# 12_RK3568_OSCPLLPMUIO.net
KiCad netlist of a schematic drawn in Altium Designer
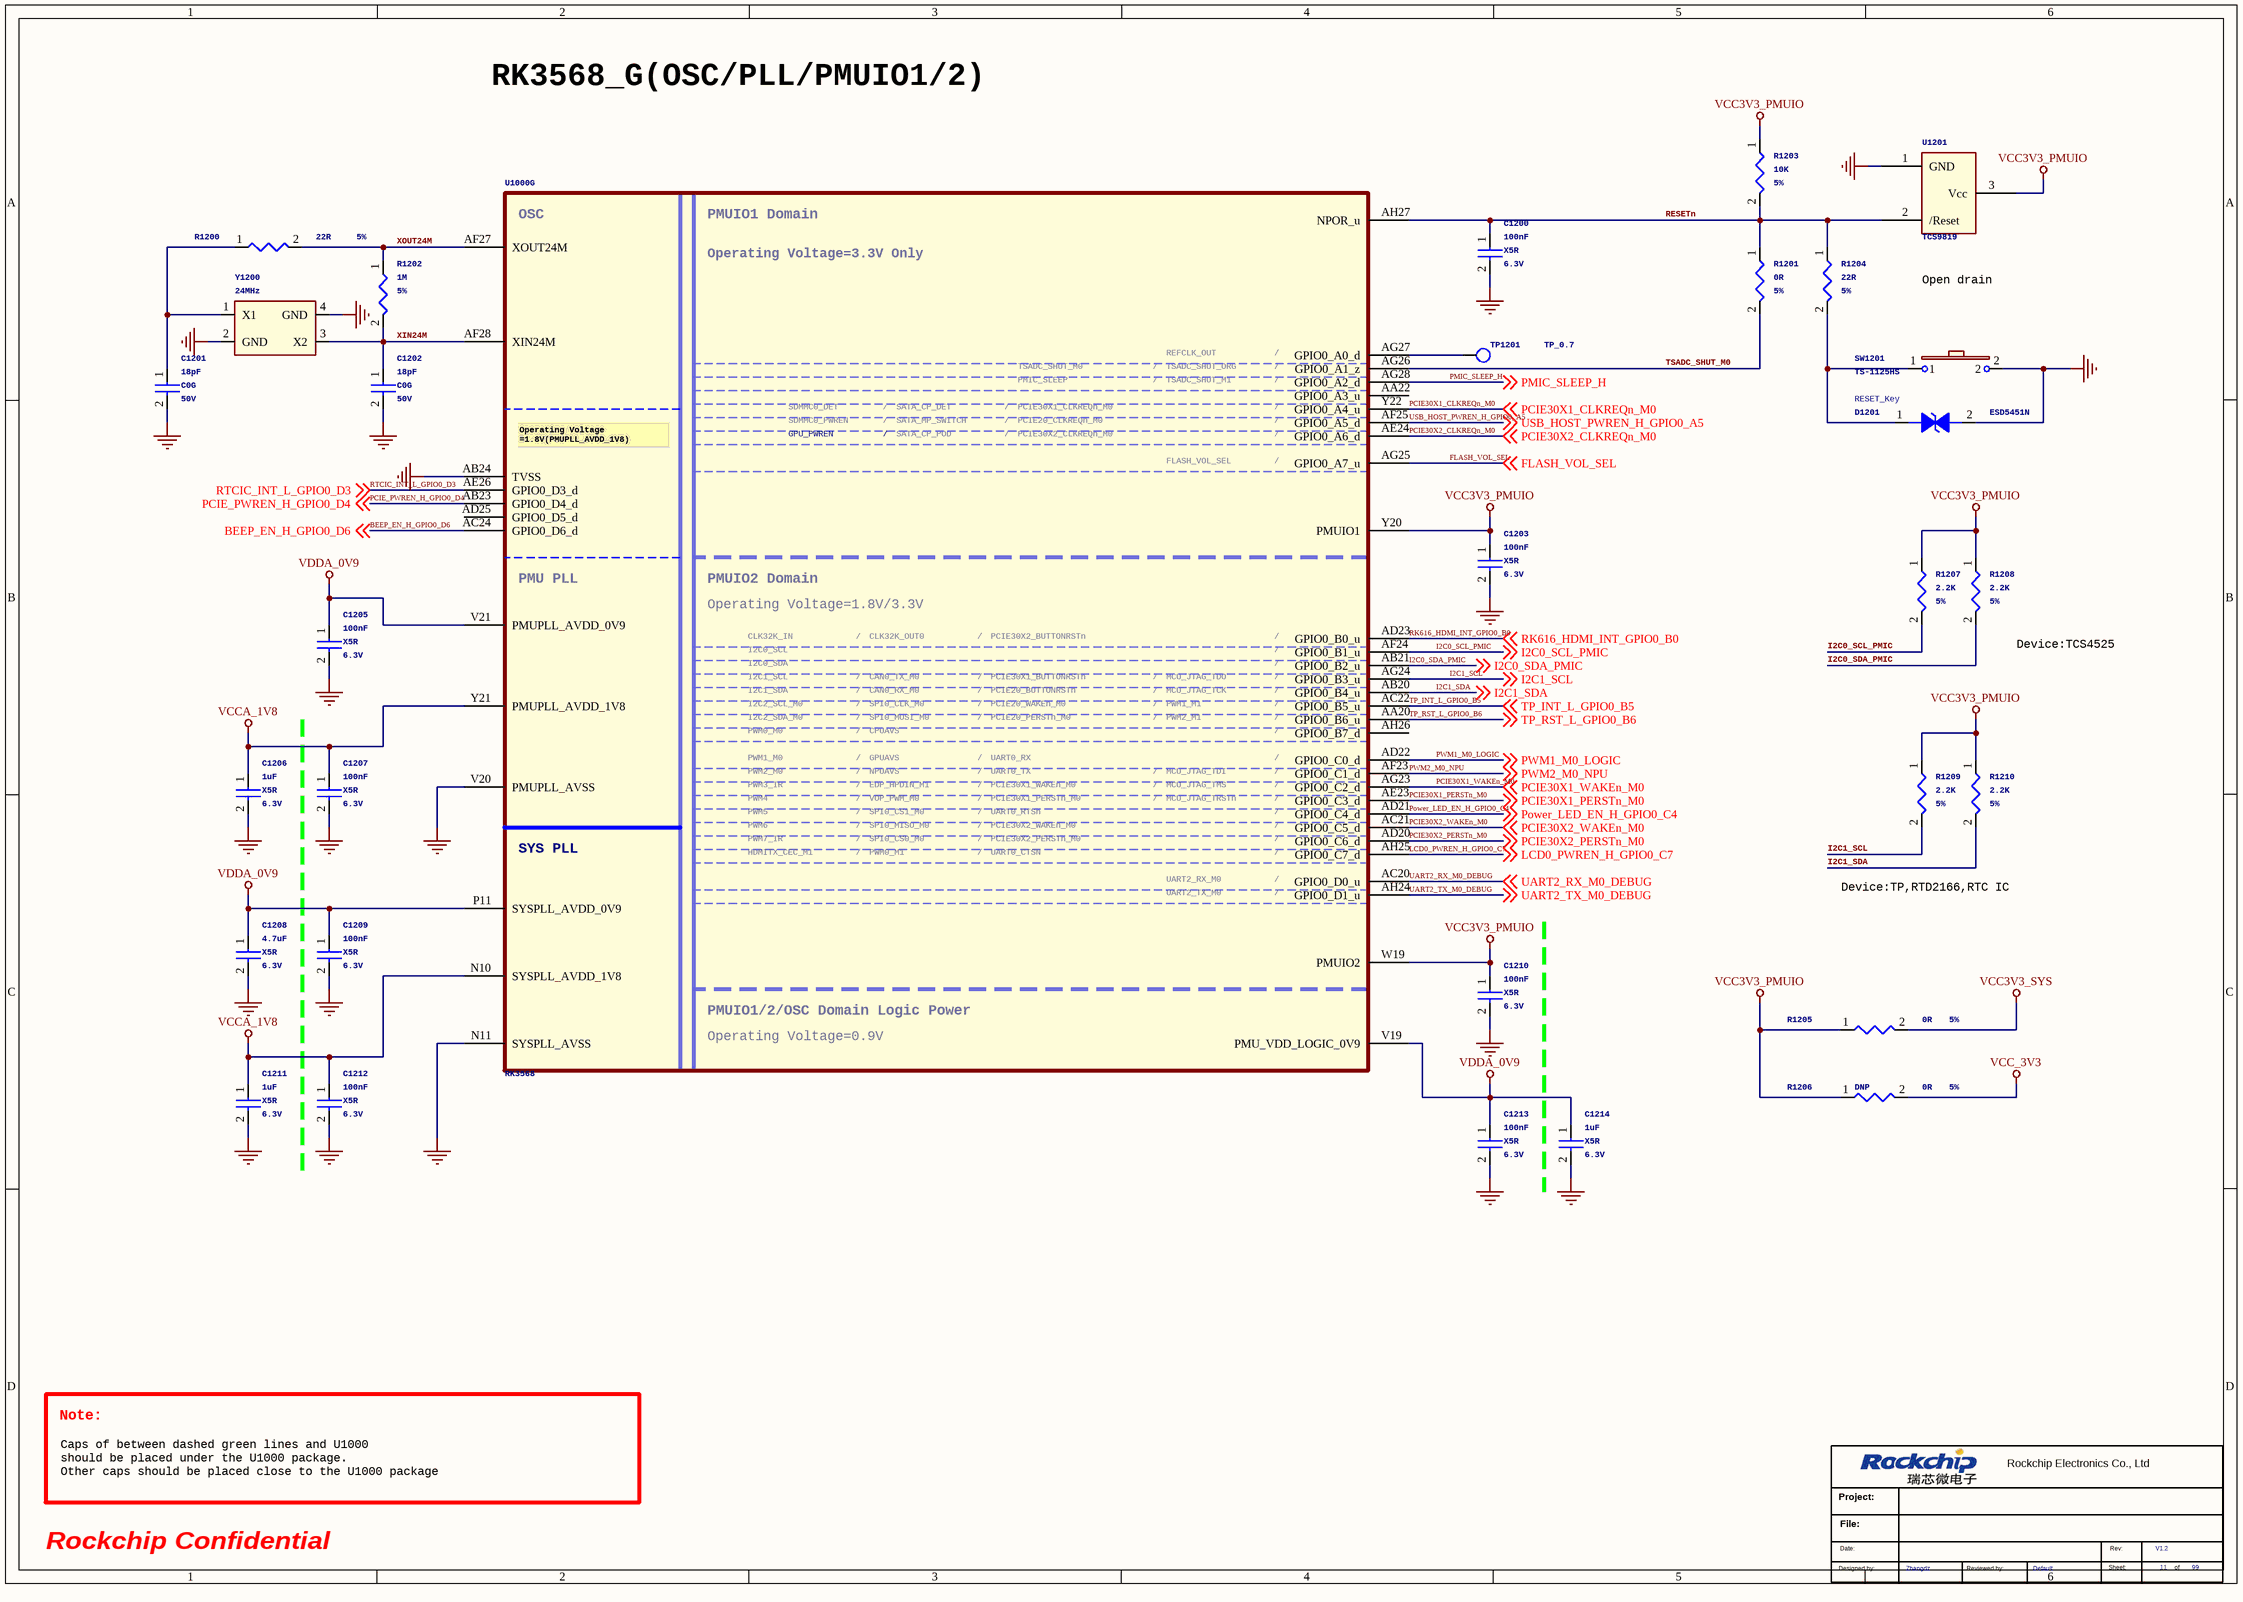
[diagram p0: 12.RK3568_OSCPLLPMUIO.SchDoc]

(export (version "E")
  (design (tool "Eeschema 10.0.6"))
  (components
    (comp (ref "*")
      (value "Rockchip_new")
      (fields
        (field (name "SCHEMATIC PAGE COUNT") "99")
        (field (name "SCHEMATIC PAGE NUMBER") "11")
        (field (name "DESIGNER") "Zhangdz")
        (field (name "REVISION") "V1.2")
        (field (name "CHECK") "Default")
      )
      (libsource (lib "*") (part "Rockchip_new"))
    )
    (comp (ref "C1200")
      (value "100nF")
      (footprint "C0201")
      (description "cap,100.00nF,+/-10%,6.3V,X5R,C0201")
      (fields
        (field (name "VOLTAGE") "6.3V")
        (field (name "DIELECTRIC") "X5R")
        (field (name "TOLERANCE") "10%")
        (field (name "MANUFACTURER") "TDK")
        (field (name "CREATED BY") "JJJ")
      )
      (libsource (lib "*") (part "CAP NP"))
    )
    (comp (ref "C1201")
      (value "18pF")
      (footprint "C0402")
      (description "cap,18.00pF,+/-5%,50V,C0G,C0402")
      (fields
        (field (name "VOLTAGE") "50V")
        (field (name "DIELECTRIC") "C0G")
        (field (name "TOLERANCE") "5%")
        (field (name "MANUFACTURER") "TDK")
        (field (name "CREATED BY") "JJJ")
      )
      (libsource (lib "*") (part "CAP NP"))
    )
    (comp (ref "C1202")
      (value "18pF")
      (footprint "C0402")
      (description "cap,18.00pF,+/-5%,50V,C0G,C0402")
      (fields
        (field (name "VOLTAGE") "50V")
        (field (name "DIELECTRIC") "C0G")
        (field (name "MANUFACTURER") "TDK")
        (field (name "TOLERANCE") "5%")
        (field (name "CREATED BY") "JJJ")
      )
      (libsource (lib "*") (part "CAP NP"))
    )
    (comp (ref "C1203")
      (value "100nF")
      (footprint "C0201")
      (description "cap,100.00nF,+/-10%,6.3V,X5R,C0201")
      (fields
        (field (name "VOLTAGE") "6.3V")
        (field (name "DIELECTRIC") "X5R")
        (field (name "MANUFACTURER") "TDK")
        (field (name "TOLERANCE") "10%")
        (field (name "CREATED BY") "JJJ")
      )
      (libsource (lib "*") (part "CAP NP"))
    )
    (comp (ref "C1205")
      (value "100nF")
      (footprint "C0201")
      (description "cap,100.00nF,+/-10%,6.3V,X5R,C0201")
      (fields
        (field (name "VOLTAGE") "6.3V")
        (field (name "DIELECTRIC") "X5R")
        (field (name "MANUFACTURER") "TDK")
        (field (name "TOLERANCE") "10%")
        (field (name "CREATED BY") "JJJ")
      )
      (libsource (lib "*") (part "CAP NP"))
    )
    (comp (ref "C1206")
      (value "1uF")
      (footprint "C0402")
      (description "cap,1.00uF,+/-10%,6.3V,X5R,C0402")
      (fields
        (field (name "VOLTAGE") "6.3V")
        (field (name "DIELECTRIC") "X5R")
        (field (name "MANUFACTURER") "TDK")
        (field (name "TOLERANCE") "10%")
        (field (name "CREATED BY") "JJJ")
      )
      (libsource (lib "*") (part "CAP NP"))
    )
    (comp (ref "C1207")
      (value "100nF")
      (footprint "C0201")
      (description "cap,100.00nF,+/-10%,6.3V,X5R,C0201")
      (fields
        (field (name "VOLTAGE") "6.3V")
        (field (name "DIELECTRIC") "X5R")
        (field (name "TOLERANCE") "10%")
        (field (name "MANUFACTURER") "TDK")
        (field (name "CREATED BY") "JJJ")
      )
      (libsource (lib "*") (part "CAP NP"))
    )
    (comp (ref "C1208")
      (value "4.7uF")
      (footprint "C0402")
      (description "cap,4.70uF,+/-10%,6.3V,X5R,C0402")
      (fields
        (field (name "VOLTAGE") "6.3V")
        (field (name "DIELECTRIC") "X5R")
        (field (name "TOLERANCE") "10%")
        (field (name "MANUFACTURER") "TDK")
        (field (name "CREATED BY") "JJJ")
      )
      (libsource (lib "*") (part "CAP NP"))
    )
    (comp (ref "C1209")
      (value "100nF")
      (footprint "C0201")
      (description "cap,100.00nF,+/-10%,6.3V,X5R,C0201")
      (fields
        (field (name "VOLTAGE") "6.3V")
        (field (name "DIELECTRIC") "X5R")
        (field (name "MANUFACTURER") "TDK")
        (field (name "TOLERANCE") "10%")
        (field (name "CREATED BY") "JJJ")
      )
      (libsource (lib "*") (part "CAP NP"))
    )
    (comp (ref "C1210")
      (value "100nF")
      (footprint "C0201")
      (description "cap,100.00nF,+/-10%,6.3V,X5R,C0201")
      (fields
        (field (name "VOLTAGE") "6.3V")
        (field (name "DIELECTRIC") "X5R")
        (field (name "MANUFACTURER") "TDK")
        (field (name "TOLERANCE") "10%")
        (field (name "CREATED BY") "JJJ")
      )
      (libsource (lib "*") (part "CAP NP"))
    )
    (comp (ref "C1211")
      (value "1uF")
      (footprint "C0402")
      (description "cap,1.00uF,+/-10%,6.3V,X5R,C0402")
      (fields
        (field (name "VOLTAGE") "6.3V")
        (field (name "DIELECTRIC") "X5R")
        (field (name "MANUFACTURER") "TDK")
        (field (name "TOLERANCE") "10%")
        (field (name "CREATED BY") "JJJ")
      )
      (libsource (lib "*") (part "CAP NP"))
    )
    (comp (ref "C1212")
      (value "100nF")
      (footprint "C0201")
      (description "cap,100.00nF,+/-10%,6.3V,X5R,C0201")
      (fields
        (field (name "VOLTAGE") "6.3V")
        (field (name "DIELECTRIC") "X5R")
        (field (name "TOLERANCE") "10%")
        (field (name "MANUFACTURER") "TDK")
        (field (name "CREATED BY") "JJJ")
      )
      (libsource (lib "*") (part "CAP NP"))
    )
    (comp (ref "C1213")
      (value "100nF")
      (footprint "C0201")
      (description "cap,100.00nF,+/-10%,6.3V,X5R,C0201")
      (fields
        (field (name "VOLTAGE") "6.3V")
        (field (name "DIELECTRIC") "X5R")
        (field (name "TOLERANCE") "10%")
        (field (name "MANUFACTURER") "TDK")
        (field (name "CREATED BY") "JJJ")
      )
      (libsource (lib "*") (part "CAP NP"))
    )
    (comp (ref "C1214")
      (value "1uF")
      (footprint "C0402")
      (description "cap,1.00uF,+/-10%,6.3V,X5R,C0402")
      (fields
        (field (name "VOLTAGE") "6.3V")
        (field (name "DIELECTRIC") "X5R")
        (field (name "TOLERANCE") "10%")
        (field (name "MANUFACTURER") "TDK")
        (field (name "CREATED BY") "JJJ")
      )
      (libsource (lib "*") (part "CAP NP"))
    )
    (comp (ref "D1201")
      (value "ESD5451N")
      (footprint "ESD0402")
      (description "1-Line, Bi-directional, Transient Voltage Suppressors.17.5pF.")
      (fields (field (name "MANUFACTURER") "WillSemi(韦尔半导体)") (field (name "CREATED BY") "JJJ"))
      (libsource (lib "*") (part "DIODE BI_DIR TRIG"))
    )
    (comp (ref "R1200")
      (value "22R")
      (footprint "R0402")
      (description "通用厚膜电阻,22R,+/-5%,R0402,1/16W.")
      (fields
        (field (name "TOLERANCE") "5%")
        (field (name "MANUFACTURER") "YAGEO")
        (field (name "CREATED BY") "YTL")
      )
      (libsource (lib "*") (part "RESISTOR"))
    )
    (comp (ref "R1201")
      (value "0R")
      (footprint "R0402")
      (description "通用厚膜电阻,0R,+/-5%,R0402,1/16W.")
      (fields
        (field (name "TOLERANCE") "5%")
        (field (name "MANUFACTURER") "YAGEO")
        (field (name "CREATED BY") "YTL")
      )
      (libsource (lib "*") (part "RESISTOR"))
    )
    (comp (ref "R1202")
      (value "1M")
      (footprint "R0402")
      (description "通用厚膜电阻,1M,+/-5%,R0402,1/16W.")
      (fields
        (field (name "TOLERANCE") "5%")
        (field (name "MANUFACTURER") "YAGEO")
        (field (name "CREATED BY") "YTL")
      )
      (libsource (lib "*") (part "RESISTOR"))
    )
    (comp (ref "R1203")
      (value "10K")
      (footprint "R0402")
      (description "通用厚膜电阻,10K,+/-5%,R0402,1/16W.")
      (fields
        (field (name "TOLERANCE") "5%")
        (field (name "MANUFACTURER") "YAGEO")
        (field (name "CREATED BY") "YTL")
      )
      (libsource (lib "*") (part "RESISTOR"))
    )
    (comp (ref "R1204")
      (value "22R")
      (footprint "R0402")
      (description "通用厚膜电阻,22R,+/-5%,R0402,1/16W.")
      (fields
        (field (name "TOLERANCE") "5%")
        (field (name "MANUFACTURER") "YAGEO")
        (field (name "CREATED BY") "YTL")
      )
      (libsource (lib "*") (part "RESISTOR"))
    )
    (comp (ref "R1205")
      (value "0R")
      (footprint "R0402")
      (description "通用厚膜电阻,0R,+/-5%,R0402,1/16W.")
      (fields
        (field (name "TOLERANCE") "5%")
        (field (name "MANUFACTURER") "YAGEO")
        (field (name "CREATED BY") "YTL")
      )
      (libsource (lib "*") (part "RESISTOR"))
    )
    (comp (ref "R1206")
      (value "0R")
      (footprint "R0402")
      (description "通用厚膜电阻,0R,+/-5%,R0402,1/16W.")
      (fields
        (field (name "TOLERANCE") "5%")
        (field (name "OPTION") "DNP")
        (field (name "MANUFACTURER") "YAGEO")
        (field (name "CREATED BY") "YTL")
      )
      (libsource (lib "*") (part "RESISTOR"))
    )
    (comp (ref "R1207")
      (value "2.2K")
      (footprint "R0402")
      (description "通用厚膜电阻,2K2,+/-5%,R0402,1/16W.")
      (fields
        (field (name "TOLERANCE") "5%")
        (field (name "MANUFACTURER") "YAGEO")
        (field (name "CREATED BY") "YTL")
      )
      (libsource (lib "*") (part "RESISTOR"))
    )
    (comp (ref "R1208")
      (value "2.2K")
      (footprint "R0402")
      (description "通用厚膜电阻,2K2,+/-5%,R0402,1/16W.")
      (fields
        (field (name "TOLERANCE") "5%")
        (field (name "MANUFACTURER") "YAGEO")
        (field (name "CREATED BY") "YTL")
      )
      (libsource (lib "*") (part "RESISTOR"))
    )
    (comp (ref "R1209")
      (value "2.2K")
      (footprint "R0402")
      (description "通用厚膜电阻,2K2,+/-5%,R0402,1/16W.")
      (fields
        (field (name "TOLERANCE") "5%")
        (field (name "MANUFACTURER") "YAGEO")
        (field (name "CREATED BY") "YTL")
      )
      (libsource (lib "*") (part "RESISTOR"))
    )
    (comp (ref "R1210")
      (value "2.2K")
      (footprint "R0402")
      (description "通用厚膜电阻,2K2,+/-5%,R0402,1/16W.")
      (fields
        (field (name "TOLERANCE") "5%")
        (field (name "MANUFACTURER") "YAGEO")
        (field (name "CREATED BY") "YTL")
      )
      (libsource (lib "*") (part "RESISTOR"))
    )
    (comp (ref "SW1201")
      (value "TS-1125HS")
      (footprint "SW2_6R00X3R70X2R50")
      (description "2脚贴片，6MMx3.7MM按键")
      (fields
        (field (name "OPTION") "RESET_Key")
        (field (name "MANUFACTURER") "褀华电子")
        (field (name "CREATED BY") "YWQ")
      )
      (libsource (lib "*") (part "KEY_2PIN"))
    )
    (comp (ref "TP1201")
      (value "TP_0.7")
      (footprint "TP_0R70")
      (description "Test Point 0.7mm")
      (fields (field (name "CREATED BY") "JJJ"))
      (libsource (lib "*") (part "TP"))
    )
    (comp (ref "U1000")
      (value "RK3568")
      (footprint "BGA636_19R00X19R00X1R20")
      (description "ROCKCHIP SOC")
      (fields (field (name "MANUFACTURER") "Rockchip (瑞芯微)") (field (name "CREATED BY") "JJJ"))
      (libsource (lib "*") (part "SOC_RK3568"))
    )
    (comp (ref "U1201")
      (value "TCS9819")
      (footprint "SOT_23")
      (description "Ultra-Small Built-In Delay High-Precision Voltage Detector")
      (fields (field (name "MANUFACTURER") "Chipower（芯力微）") (field (name "CREATED BY") "JJJ"))
      (libsource (lib "*") (part "Voltage_Detector_CE8809"))
    )
    (comp (ref "Y1200")
      (value "24MHz")
      (footprint "CRY4_3R20X2R50X0R80")
      (description "无源晶振，24M，3225,±10ppm，8pF，Hosonic")
      (fields (field (name "MANUFACTURER") "Hosonic(鸿星电子)") (field (name "CREATED BY") "JJJ"))
      (libsource (lib "*") (part "CRYSTAL_4P"))
    )
  )
  (nets
    (net (code "1") (name "/RESETn") (class "Default")
      (node (ref "C1200") (pin "1") (pinfunction "1_1") (pintype "passive"))
      (node (ref "R1201") (pin "1") (pinfunction "1_1") (pintype "passive"))
      (node (ref "R1203") (pin "2") (pinfunction "2_2") (pintype "passive"))
      (node (ref "R1204") (pin "1") (pinfunction "1_1") (pintype "passive"))
      (node (ref "U1000") (pin "AH27") (pinfunction "NPOR_u_AH27") (pintype "passive"))
      (node (ref "U1201") (pin "2") (pinfunction "/Reset_2") (pintype "passive"))
    )
    (net (code "2") (name "/TSADC_SHUT_M0") (class "Default")
      (node (ref "R1201") (pin "2") (pinfunction "2_2") (pintype "passive"))
      (node (ref "U1000") (pin "AG26") (pinfunction "GPIO0_A1_z_AG26") (pintype "passive"))
    )
    (net (code "3") (name "/XIN24M") (class "Default")
      (node (ref "C1202") (pin "1") (pinfunction "1_1") (pintype "passive"))
      (node (ref "R1202") (pin "2") (pinfunction "2_2") (pintype "passive"))
      (node (ref "U1000") (pin "AF28") (pinfunction "XIN24M_AF28") (pintype "passive"))
      (node (ref "Y1200") (pin "3") (pinfunction "X2_3") (pintype "passive"))
    )
    (net (code "4") (name "/XOUT24M") (class "Default")
      (node (ref "R1200") (pin "2") (pinfunction "2_2") (pintype "passive"))
      (node (ref "R1202") (pin "1") (pinfunction "1_1") (pintype "passive"))
      (node (ref "U1000") (pin "AF27") (pinfunction "XOUT24M_AF27") (pintype "passive"))
    )
    (net (code "5") (name "BEEP_EN_H_GPIO0_D6") (class "Default")
      (node (ref "U1000") (pin "AC24") (pinfunction "GPIO0_D6_d_AC24") (pintype "passive"))
    )
    (net (code "6") (name "FLASH_VOL_SEL") (class "Default")
      (node (ref "U1000") (pin "AG25") (pinfunction "GPIO0_A7_u_AG25") (pintype "passive"))
    )
    (net (code "7") (name "GND") (class "Default")
      (node (ref "C1200") (pin "2") (pinfunction "2_2") (pintype "passive"))
      (node (ref "C1201") (pin "2") (pinfunction "2_2") (pintype "passive"))
      (node (ref "C1202") (pin "2") (pinfunction "2_2") (pintype "passive"))
      (node (ref "C1203") (pin "2") (pinfunction "2_2") (pintype "passive"))
      (node (ref "C1205") (pin "2") (pinfunction "2_2") (pintype "passive"))
      (node (ref "C1206") (pin "2") (pinfunction "2_2") (pintype "passive"))
      (node (ref "C1207") (pin "2") (pinfunction "2_2") (pintype "passive"))
      (node (ref "C1208") (pin "2") (pinfunction "2_2") (pintype "passive"))
      (node (ref "C1209") (pin "2") (pinfunction "2_2") (pintype "passive"))
      (node (ref "C1210") (pin "2") (pinfunction "2_2") (pintype "passive"))
      (node (ref "C1211") (pin "2") (pinfunction "2_2") (pintype "passive"))
      (node (ref "C1212") (pin "2") (pinfunction "2_2") (pintype "passive"))
      (node (ref "C1213") (pin "2") (pinfunction "2_2") (pintype "passive"))
      (node (ref "C1214") (pin "2") (pinfunction "2_2") (pintype "passive"))
      (node (ref "D1201") (pin "2") (pinfunction "2_2") (pintype "passive"))
      (node (ref "SW1201") (pin "2") (pinfunction "2_2") (pintype "passive"))
      (node (ref "U1000") (pin "AB24") (pinfunction "TVSS_AB24") (pintype "passive"))
      (node (ref "U1000") (pin "N11") (pinfunction "SYSPLL_AVSS_N11") (pintype "passive"))
      (node (ref "U1000") (pin "V20") (pinfunction "PMUPLL_AVSS_V20") (pintype "passive"))
      (node (ref "U1201") (pin "1") (pinfunction "GND_1") (pintype "passive"))
      (node (ref "Y1200") (pin "2") (pinfunction "GND_2") (pintype "power_in"))
      (node (ref "Y1200") (pin "4") (pinfunction "GND_4") (pintype "power_in"))
    )
    (net (code "8") (name "I2C0_SCL_PMIC") (class "Default")
      (node (ref "R1207") (pin "2") (pinfunction "2_2") (pintype "passive"))
      (node (ref "U1000") (pin "AF24") (pinfunction "GPIO0_B1_u_AF24") (pintype "passive"))
    )
    (net (code "9") (name "I2C0_SDA_PMIC") (class "Default")
      (node (ref "R1208") (pin "2") (pinfunction "2_2") (pintype "passive"))
      (node (ref "U1000") (pin "AB21") (pinfunction "GPIO0_B2_u_AB21") (pintype "passive"))
    )
    (net (code "10") (name "I2C1_SCL") (class "Default")
      (node (ref "R1209") (pin "2") (pinfunction "2_2") (pintype "passive"))
      (node (ref "U1000") (pin "AG24") (pinfunction "GPIO0_B3_u_AG24") (pintype "passive"))
    )
    (net (code "11") (name "I2C1_SDA") (class "Default")
      (node (ref "R1210") (pin "2") (pinfunction "2_2") (pintype "passive"))
      (node (ref "U1000") (pin "AB20") (pinfunction "GPIO0_B4_u_AB20") (pintype "passive"))
    )
    (net (code "12") (name "LCD0_PWREN_H_GPIO0_C7") (class "Default")
      (node (ref "U1000") (pin "AH25") (pinfunction "GPIO0_C7_d_AH25") (pintype "passive"))
    )
    (net (code "13") (name "Net-(D1201-Pad1)") (class "Default")
      (node (ref "D1201") (pin "1") (pinfunction "1_1") (pintype "passive"))
      (node (ref "R1204") (pin "2") (pinfunction "2_2") (pintype "passive"))
      (node (ref "SW1201") (pin "1") (pinfunction "1_1") (pintype "passive"))
    )
    (net (code "14") (name "Net-(U1000G-GPIO0_A0_d)") (class "Default")
      (node (ref "TP1201") (pin "1") (pinfunction "1_1") (pintype "passive"))
      (node (ref "U1000") (pin "AG27") (pinfunction "GPIO0_A0_d_AG27") (pintype "passive"))
    )
    (net (code "15") (name "Net-(Y1200-X1)") (class "Default")
      (node (ref "C1201") (pin "1") (pinfunction "1_1") (pintype "passive"))
      (node (ref "R1200") (pin "1") (pinfunction "1_1") (pintype "passive"))
      (node (ref "Y1200") (pin "1") (pinfunction "X1_1") (pintype "passive"))
    )
    (net (code "16") (name "PCIE30X1_CLKREQn_M0") (class "Default")
      (node (ref "U1000") (pin "Y22") (pinfunction "GPIO0_A4_u_Y22") (pintype "passive"))
    )
    (net (code "17") (name "PCIE30X1_PERSTn_M0") (class "Default")
      (node (ref "U1000") (pin "AE23") (pinfunction "GPIO0_C3_d_AE23") (pintype "passive"))
    )
    (net (code "18") (name "PCIE30X1_WAKEn_M0") (class "Default")
      (node (ref "U1000") (pin "AG23") (pinfunction "GPIO0_C2_d_AG23") (pintype "passive"))
    )
    (net (code "19") (name "PCIE30X2_CLKREQn_M0") (class "Default")
      (node (ref "U1000") (pin "AE24") (pinfunction "GPIO0_A6_d_AE24") (pintype "passive"))
    )
    (net (code "20") (name "PCIE30X2_PERSTn_M0") (class "Default")
      (node (ref "U1000") (pin "AD20") (pinfunction "GPIO0_C6_d_AD20") (pintype "passive"))
    )
    (net (code "21") (name "PCIE30X2_WAKEn_M0") (class "Default")
      (node (ref "U1000") (pin "AC21") (pinfunction "GPIO0_C5_d_AC21") (pintype "passive"))
    )
    (net (code "22") (name "PCIE_PWREN_H_GPIO0_D4") (class "Default")
      (node (ref "U1000") (pin "AB23") (pinfunction "GPIO0_D4_d_AB23") (pintype "passive"))
    )
    (net (code "23") (name "PMIC_SLEEP_H") (class "Default")
      (node (ref "U1000") (pin "AG28") (pinfunction "GPIO0_A2_d_AG28") (pintype "passive"))
    )
    (net (code "24") (name "PWM1_M0_LOGIC") (class "Default")
      (node (ref "U1000") (pin "AD22") (pinfunction "GPIO0_C0_d_AD22") (pintype "passive"))
    )
    (net (code "25") (name "PWM2_M0_NPU") (class "Default")
      (node (ref "U1000") (pin "AF23") (pinfunction "GPIO0_C1_d_AF23") (pintype "passive"))
    )
    (net (code "26") (name "Power_LED_EN_H_GPIO0_C4") (class "Default")
      (node (ref "U1000") (pin "AD21") (pinfunction "GPIO0_C4_d_AD21") (pintype "passive"))
    )
    (net (code "27") (name "RK616_HDMI_INT_GPIO0_B0") (class "Default")
      (node (ref "U1000") (pin "AD23") (pinfunction "GPIO0_B0_u_AD23") (pintype "passive"))
    )
    (net (code "28") (name "RTCIC_INT_L_GPIO0_D3") (class "Default")
      (node (ref "U1000") (pin "AE26") (pinfunction "GPIO0_D3_d_AE26") (pintype "passive"))
    )
    (net (code "29") (name "TP_INT_L_GPIO0_B5") (class "Default")
      (node (ref "U1000") (pin "AC22") (pinfunction "GPIO0_B5_u_AC22") (pintype "passive"))
    )
    (net (code "30") (name "TP_RST_L_GPIO0_B6") (class "Default")
      (node (ref "U1000") (pin "AA20") (pinfunction "GPIO0_B6_u_AA20") (pintype "passive"))
    )
    (net (code "31") (name "UART2_RX_M0_DEBUG") (class "Default")
      (node (ref "U1000") (pin "AC20") (pinfunction "GPIO0_D0_u_AC20") (pintype "passive"))
    )
    (net (code "32") (name "UART2_TX_M0_DEBUG") (class "Default")
      (node (ref "U1000") (pin "AH24") (pinfunction "GPIO0_D1_u_AH24") (pintype "passive"))
    )
    (net (code "33") (name "USB_HOST_PWREN_H_GPIO0_A5") (class "Default")
      (node (ref "U1000") (pin "AF25") (pinfunction "GPIO0_A5_d_AF25") (pintype "passive"))
    )
    (net (code "34") (name "VCC3V3_PMUIO") (class "Default")
      (node (ref "C1203") (pin "1") (pinfunction "1_1") (pintype "passive"))
      (node (ref "C1210") (pin "1") (pinfunction "1_1") (pintype "passive"))
      (node (ref "R1203") (pin "1") (pinfunction "1_1") (pintype "passive"))
      (node (ref "R1205") (pin "1") (pinfunction "1_1") (pintype "passive"))
      (node (ref "R1206") (pin "1") (pinfunction "1_1") (pintype "passive"))
      (node (ref "R1207") (pin "1") (pinfunction "1_1") (pintype "passive"))
      (node (ref "R1208") (pin "1") (pinfunction "1_1") (pintype "passive"))
      (node (ref "R1209") (pin "1") (pinfunction "1_1") (pintype "passive"))
      (node (ref "R1210") (pin "1") (pinfunction "1_1") (pintype "passive"))
      (node (ref "U1000") (pin "W19") (pinfunction "PMUIO2_W19") (pintype "passive"))
      (node (ref "U1000") (pin "Y20") (pinfunction "PMUIO1_Y20") (pintype "passive"))
      (node (ref "U1201") (pin "3") (pinfunction "Vcc_3") (pintype "passive"))
    )
    (net (code "35") (name "VCC3V3_SYS") (class "Default")
      (node (ref "R1205") (pin "2") (pinfunction "2_2") (pintype "passive"))
    )
    (net (code "36") (name "VCCA_1V8") (class "Default")
      (node (ref "C1206") (pin "1") (pinfunction "1_1") (pintype "passive"))
      (node (ref "C1207") (pin "1") (pinfunction "1_1") (pintype "passive"))
      (node (ref "C1211") (pin "1") (pinfunction "1_1") (pintype "passive"))
      (node (ref "C1212") (pin "1") (pinfunction "1_1") (pintype "passive"))
      (node (ref "U1000") (pin "N10") (pinfunction "SYSPLL_AVDD_1V8_N10") (pintype "passive"))
      (node (ref "U1000") (pin "Y21") (pinfunction "PMUPLL_AVDD_1V8_Y21") (pintype "passive"))
    )
    (net (code "37") (name "VCC_3V3") (class "Default")
      (node (ref "R1206") (pin "2") (pinfunction "2_2") (pintype "passive"))
    )
    (net (code "38") (name "VDDA_0V9") (class "Default")
      (node (ref "C1205") (pin "1") (pinfunction "1_1") (pintype "passive"))
      (node (ref "C1208") (pin "1") (pinfunction "1_1") (pintype "passive"))
      (node (ref "C1209") (pin "1") (pinfunction "1_1") (pintype "passive"))
      (node (ref "C1213") (pin "1") (pinfunction "1_1") (pintype "passive"))
      (node (ref "C1214") (pin "1") (pinfunction "1_1") (pintype "passive"))
      (node (ref "U1000") (pin "P11") (pinfunction "SYSPLL_AVDD_0V9_P11") (pintype "passive"))
      (node (ref "U1000") (pin "V19") (pinfunction "PMU_VDD_LOGIC_0V9_V19") (pintype "passive"))
      (node (ref "U1000") (pin "V21") (pinfunction "PMUPLL_AVDD_0V9_V21") (pintype "passive"))
    )
    (net (code "39") (name "unconnected-(U1000G-GPIO0_A3_u-PadAA22)") (class "Default")
      (node (ref "U1000") (pin "AA22") (pinfunction "GPIO0_A3_u_AA22") (pintype "passive"))
    )
    (net (code "40") (name "unconnected-(U1000G-GPIO0_B7_d-PadAH26)") (class "Default")
      (node (ref "U1000") (pin "AH26") (pinfunction "GPIO0_B7_d_AH26") (pintype "passive"))
    )
    (net (code "41") (name "unconnected-(U1000G-GPIO0_D5_d-PadAD25)") (class "Default")
      (node (ref "U1000") (pin "AD25") (pinfunction "GPIO0_D5_d_AD25") (pintype "passive"))
    )
  )
)
